# control_board-ATSAMD21.net
KiCad netlist of a schematic drawn in EAGLE
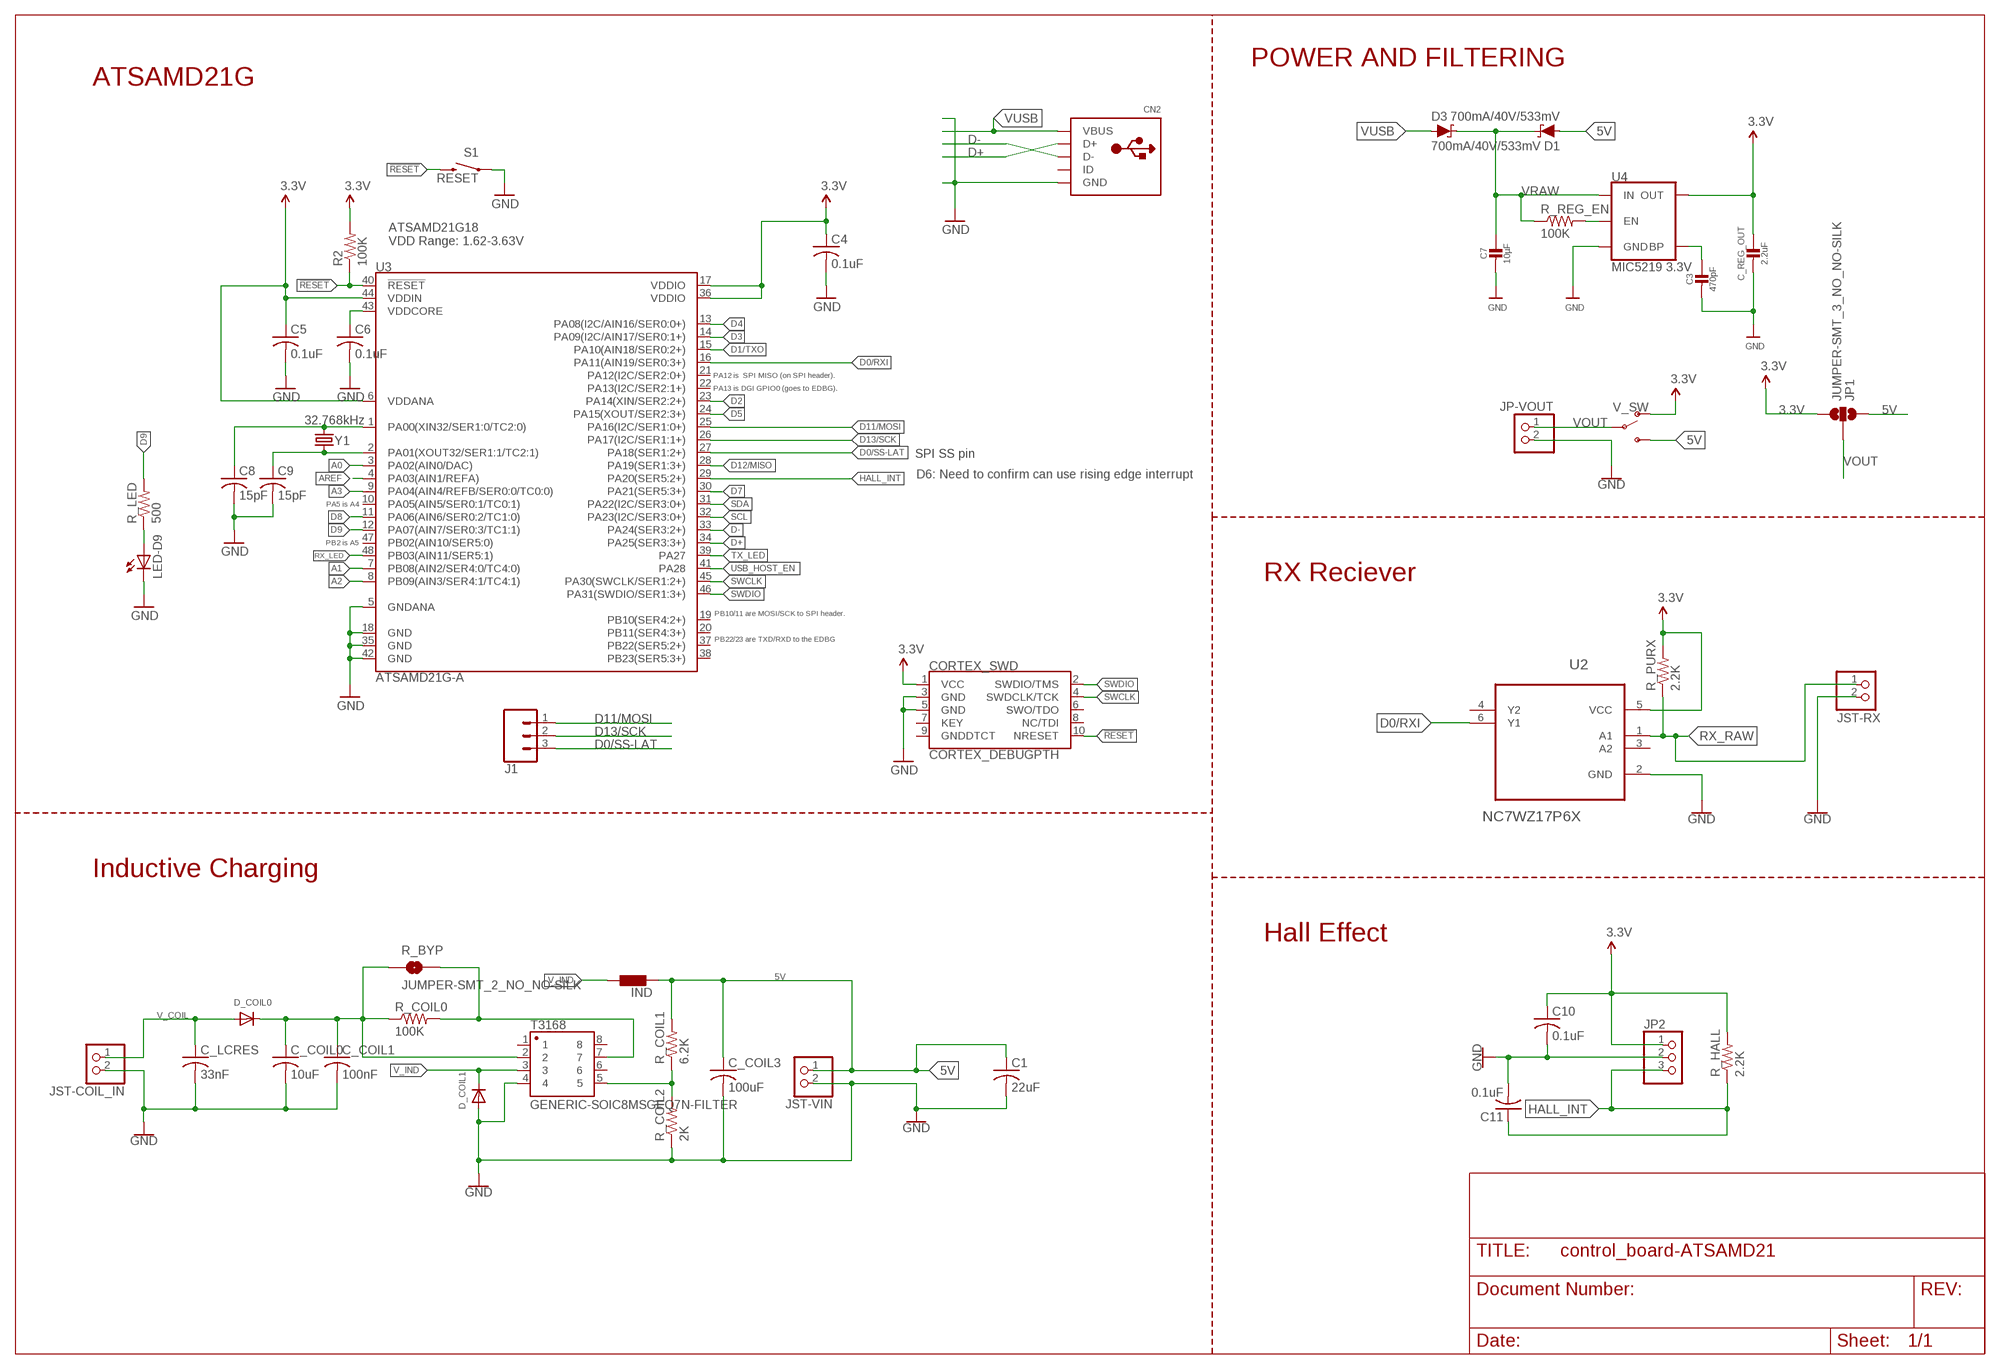
[diagram p0: schematic, sheet 1]

(export (version "E")
  (design (tool "Eeschema 10.0.6"))
  (components
    (comp (ref "C1")
      (value "22uF")
      (footprint "eagle-import:C1206")
      (libsource (lib "eagle-import") (part "C-USC1206"))
    )
    (comp (ref "C3")
      (value "470pF")
      (footprint "eagle-import:0603-NO")
      (libsource (lib "eagle-import") (part "CAP_CERAMIC0603_NO"))
    )
    (comp (ref "C4")
      (value "0.1uF")
      (footprint "eagle-import:C0603")
      (libsource (lib "eagle-import") (part "C-USC0603"))
    )
    (comp (ref "C5")
      (value "0.1uF")
      (footprint "eagle-import:C0603")
      (libsource (lib "eagle-import") (part "C-USC0603"))
    )
    (comp (ref "C6")
      (value "0.1uF")
      (footprint "eagle-import:C0603")
      (libsource (lib "eagle-import") (part "C-USC0603"))
    )
    (comp (ref "C7")
      (value "10µF")
      (footprint "eagle-import:0805-NO")
      (libsource (lib "eagle-import") (part "CAP_CERAMIC0805-NOOUTLINE"))
    )
    (comp (ref "C8")
      (value "15pF")
      (footprint "eagle-import:C0603")
      (libsource (lib "eagle-import") (part "C-USC0603"))
    )
    (comp (ref "C9")
      (value "15pF")
      (footprint "eagle-import:C0603")
      (libsource (lib "eagle-import") (part "C-USC0603"))
    )
    (comp (ref "C10")
      (value "0.1uF")
      (footprint "eagle-import:C0603")
      (libsource (lib "eagle-import") (part "C-USC0603"))
    )
    (comp (ref "C11")
      (value "0.1uF")
      (footprint "eagle-import:C0603")
      (libsource (lib "eagle-import") (part "C-USC0603"))
    )
    (comp (ref "CN2")
      (value "USBTHM")
      (footprint "eagle-import:USB-MINIB-THM")
      (libsource (lib "eagle-import") (part "USBTHM"))
    )
    (comp (ref "CORTEX_SWD")
      (value "CORTEX_DEBUGPTH")
      (footprint "eagle-import:2X5-PTH-1.27MM")
      (libsource (lib "eagle-import") (part "CORTEX_DEBUGPTH"))
    )
    (comp (ref "C_COIL0")
      (value "10uF")
      (footprint "eagle-import:C1206")
      (libsource (lib "eagle-import") (part "C-USC1206"))
    )
    (comp (ref "C_COIL1")
      (value "100nF")
      (footprint "eagle-import:C1206")
      (libsource (lib "eagle-import") (part "C-USC1206"))
    )
    (comp (ref "C_COIL3")
      (value "100uF")
      (footprint "eagle-import:C1206")
      (libsource (lib "eagle-import") (part "C-USC1206"))
    )
    (comp (ref "C_LCRES")
      (value "33nF")
      (footprint "eagle-import:C1206")
      (libsource (lib "eagle-import") (part "C-USC1206"))
    )
    (comp (ref "C_REG_OUT")
      (value "2.2uF")
      (footprint "eagle-import:0805-NO")
      (libsource (lib "eagle-import") (part "CAP_CERAMIC0805-NOOUTLINE"))
    )
    (comp (ref "D1")
      (value "700mA/40V/533mV")
      (footprint "eagle-import:SOT23-3")
      (libsource (lib "eagle-import") (part "DIODE-SCHOTTKY-ZLLS500"))
    )
    (comp (ref "D3")
      (value "700mA/40V/533mV")
      (footprint "eagle-import:SOT23-3")
      (libsource (lib "eagle-import") (part "DIODE-SCHOTTKY-ZLLS500"))
    )
    (comp (ref "D_COIL0")
      (value "DIODESMA")
      (footprint "eagle-import:SMADIODE")
      (libsource (lib "eagle-import") (part "DIODESMA"))
    )
    (comp (ref "D_COIL1")
      (value "DIODE_SOD-123FL")
      (footprint "eagle-import:SOD-123FL")
      (libsource (lib "eagle-import") (part "DIODE_SOD-123FL"))
    )
    (comp (ref "IND")
      (value "LL3230M")
      (footprint "eagle-import:L3230M")
      (libsource (lib "eagle-import") (part "LL3230M"))
    )
    (comp (ref "J1")
      (value "CONN_031X03_NO_SILK")
      (footprint "eagle-import:1X03_NO_SILK")
      (libsource (lib "eagle-import") (part "CONN_031X03_NO_SILK"))
    )
    (comp (ref "JP-VOUT")
      (value "PINHD-1X2")
      (footprint "eagle-import:1X02")
      (libsource (lib "eagle-import") (part "PINHD-1X2"))
    )
    (comp (ref "JP1")
      (value "JUMPER-SMT_3_NO_NO-SILK")
      (footprint "eagle-import:SMT-JUMPER_3_NO_NO-SILK")
      (libsource (lib "eagle-import") (part "JUMPER-SMT_3_NO_NO-SILK"))
    )
    (comp (ref "JP2")
      (value "PINHD-1X3")
      (footprint "eagle-import:1X03")
      (libsource (lib "eagle-import") (part "PINHD-1X3"))
    )
    (comp (ref "JST-COIL_IN")
      (value "JST_2PIN-THM-RA")
      (footprint "eagle-import:JST-PH-2-THM-RA")
      (libsource (lib "eagle-import") (part "JST_2PIN-THM-RA"))
    )
    (comp (ref "JST-RX")
      (value "JST_2PIN-THM-RA")
      (footprint "eagle-import:JST-PH-2-THM-RA")
      (libsource (lib "eagle-import") (part "JST_2PIN-THM-RA"))
    )
    (comp (ref "JST-VIN")
      (value "JST_2PIN-THM-RA")
      (footprint "eagle-import:JST-PH-2-THM-RA")
      (libsource (lib "eagle-import") (part "JST_2PIN-THM-RA"))
    )
    (comp (ref "LED-D9")
      (value "LEDCHIPLED_0603")
      (footprint "eagle-import:CHIPLED_0603")
      (libsource (lib "eagle-import") (part "LEDCHIPLED_0603"))
    )
    (comp (ref "R2")
      (value "100K")
      (footprint "eagle-import:0603-RES")
      (libsource (lib "eagle-import") (part "10KOHM-1/10W-1%(0603)0603"))
    )
    (comp (ref "R_BYP")
      (value "JUMPER-SMT_2_NO_NO-SILK")
      (footprint "eagle-import:SMT-JUMPER_2_NO_NO-SILK")
      (libsource (lib "eagle-import") (part "JUMPER-SMT_2_NO_NO-SILK"))
    )
    (comp (ref "R_COIL0")
      (value "100K")
      (footprint "eagle-import:R0603")
      (libsource (lib "eagle-import") (part "R-US_R0603"))
    )
    (comp (ref "R_COIL1")
      (value "6.2K")
      (footprint "eagle-import:R0603")
      (libsource (lib "eagle-import") (part "R-US_R0603"))
    )
    (comp (ref "R_COIL2")
      (value "2K")
      (footprint "eagle-import:R0603")
      (libsource (lib "eagle-import") (part "R-US_R0603"))
    )
    (comp (ref "R_HALL")
      (value "2.2K")
      (footprint "eagle-import:R0805")
      (libsource (lib "eagle-import") (part "R-US_R0805"))
    )
    (comp (ref "R_LED")
      (value "500")
      (footprint "eagle-import:R0603")
      (libsource (lib "eagle-import") (part "R-US_R0603"))
    )
    (comp (ref "R_PURX")
      (value "2.2K")
      (footprint "eagle-import:R0603")
      (libsource (lib "eagle-import") (part "R-US_R0603"))
    )
    (comp (ref "R_REG_EN")
      (value "100K")
      (footprint "eagle-import:R0603")
      (libsource (lib "eagle-import") (part "R-US_R0603"))
    )
    (comp (ref "S1")
      (value "RESET")
      (footprint "eagle-import:TACTILE_SWITCH_SMD_4.6X2.8MM")
      (libsource (lib "eagle-import") (part "SWITCH-MOMENTARY-2SMD-4.6X2.8MM"))
    )
    (comp (ref "T3168")
      (value "GENERIC-SOIC8MSGEQ7N-FILTER")
      (footprint "eagle-import:SO08")
      (libsource (lib "eagle-import") (part "GENERIC-SOIC8MSGEQ7N-FILTER"))
    )
    (comp (ref "U2")
      (value "NC7WZ17P6X")
      (footprint "eagle-import:SOT65P210X110-6N")
      (fields (field (name "MF") "Fairchild Semiconductor"))
      (libsource (lib "eagle-import") (part "NC7WZ17P6X"))
    )
    (comp (ref "U3")
      (value "ATSAMD21G-A")
      (footprint "eagle-import:TQFP-48")
      (libsource (lib "eagle-import") (part "ATSAMD21G-A"))
    )
    (comp (ref "U4")
      (value "MIC5219 3.3V")
      (footprint "eagle-import:SOT23-5")
      (libsource (lib "eagle-import") (part "V_REG_MIC52193.3V"))
    )
    (comp (ref "V_SW")
      (value "SWITCH-SPDT-SMD-RIGHT-ANGLE")
      (footprint "eagle-import:SWITCH_SPST_SMD_A")
      (libsource (lib "eagle-import") (part "SWITCH-SPDT-SMD-RIGHT-ANGLE"))
    )
    (comp (ref "Y1")
      (value "32.768kHz")
      (footprint "eagle-import:CRYSTAL-SMD-3.2X1.5MM")
      (libsource (lib "eagle-import") (part "CRYSTAL3.2X1.5MM"))
    )
  )
  (nets
    (net (code "1") (name "/VOUT") (class "Default")
      (node (ref "JP-VOUT") (pin "1") (pinfunction "1_1") (pintype "passive"))
      (node (ref "JP1") (pin "2") (pinfunction "2_2") (pintype "passive"))
      (node (ref "V_SW") (pin "2") (pinfunction "P_2") (pintype "passive"))
    )
    (net (code "2") (name "/VRAW") (class "Default")
      (node (ref "C7") (pin "1") (pinfunction "1_1") (pintype "passive"))
      (node (ref "D1") (pin "3") (pinfunction "C_3") (pintype "passive"))
      (node (ref "D3") (pin "3") (pinfunction "C_3") (pintype "passive"))
      (node (ref "R_REG_EN") (pin "1") (pinfunction "1_1") (pintype "passive"))
      (node (ref "U4") (pin "1") (pinfunction "IN_1") (pintype "input"))
    )
    (net (code "3") (name "/V_COIL") (class "Default")
      (node (ref "C_LCRES") (pin "1") (pinfunction "1_1") (pintype "passive"))
      (node (ref "D_COIL0") (pin "A") (pinfunction "A_A") (pintype "passive"))
      (node (ref "JST-COIL_IN") (pin "1") (pinfunction "2_1") (pintype "passive"))
    )
    (net (code "4") (name "/~{RESET}") (class "Default")
      (node (ref "CORTEX_SWD") (pin "10") (pinfunction "NRESET_10") (pintype "bidirectional"))
      (node (ref "R2") (pin "1") (pinfunction "1_1") (pintype "passive"))
      (node (ref "S1") (pin "3") (pinfunction "2_3") (pintype "passive"))
      (node (ref "S1") (pin "4") (pinfunction "2_4") (pintype "passive"))
      (node (ref "U3") (pin "40") (pinfunction "~{RESET}_40") (pintype "bidirectional"))
    )
    (net (code "5") (name "3.3V") (class "Default")
      (node (ref "C10") (pin "1") (pinfunction "1_1") (pintype "passive"))
      (node (ref "C4") (pin "1") (pinfunction "1_1") (pintype "passive"))
      (node (ref "C5") (pin "1") (pinfunction "1_1") (pintype "passive"))
      (node (ref "CORTEX_SWD") (pin "1") (pinfunction "VCC_1") (pintype "bidirectional"))
      (node (ref "C_REG_OUT") (pin "1") (pinfunction "1_1") (pintype "passive"))
      (node (ref "JP1") (pin "3") (pinfunction "3_3") (pintype "passive"))
      (node (ref "JP2") (pin "1") (pinfunction "1_1") (pintype "passive"))
      (node (ref "R2") (pin "2") (pinfunction "2_2") (pintype "passive"))
      (node (ref "R_HALL") (pin "2") (pinfunction "2_2") (pintype "passive"))
      (node (ref "R_PURX") (pin "2") (pinfunction "2_2") (pintype "passive"))
      (node (ref "U2") (pin "5") (pinfunction "VCC_5") (pintype "power_in"))
      (node (ref "U3") (pin "17") (pinfunction "VDDIO_17") (pintype "bidirectional"))
      (node (ref "U3") (pin "36") (pinfunction "VDDIO_36") (pintype "bidirectional"))
      (node (ref "U3") (pin "44") (pinfunction "VDDIN_44") (pintype "bidirectional"))
      (node (ref "U3") (pin "6") (pinfunction "VDDANA_6") (pintype "bidirectional"))
      (node (ref "U4") (pin "5") (pinfunction "OUT_5") (pintype "passive"))
      (node (ref "V_SW") (pin "1") (pinfunction "O_1") (pintype "passive"))
    )
    (net (code "6") (name "5V") (class "Default")
      (node (ref "C1") (pin "1") (pinfunction "1_1") (pintype "passive"))
      (node (ref "C_COIL3") (pin "1") (pinfunction "1_1") (pintype "passive"))
      (node (ref "D1") (pin "1") (pinfunction "A_1") (pintype "passive"))
      (node (ref "IND") (pin "2") (pinfunction "2_2") (pintype "passive"))
      (node (ref "JP1") (pin "1") (pinfunction "1_1") (pintype "passive"))
      (node (ref "JST-VIN") (pin "1") (pinfunction "2_1") (pintype "passive"))
      (node (ref "R_COIL1") (pin "2") (pinfunction "2_2") (pintype "passive"))
      (node (ref "V_SW") (pin "3") (pinfunction "S_3") (pintype "passive"))
    )
    (net (code "7") (name "A0") (class "Default")
      (node (ref "U3") (pin "3") (pinfunction "PA02(AIN0/DAC)_3") (pintype "bidirectional"))
    )
    (net (code "8") (name "A1") (class "Default")
      (node (ref "U3") (pin "7") (pinfunction "PB08(AIN2/SER4:0/TC4:0)_7") (pintype "bidirectional"))
    )
    (net (code "9") (name "A2") (class "Default")
      (node (ref "U3") (pin "8") (pinfunction "PB09(AIN3/SER4:1/TC4:1)_8") (pintype "bidirectional"))
    )
    (net (code "10") (name "A3") (class "Default")
      (node (ref "U3") (pin "9") (pinfunction "PA04(AIN4/REFB/SER0:0/TC0:0)_9") (pintype "bidirectional"))
    )
    (net (code "11") (name "AREF") (class "Default")
      (node (ref "U3") (pin "4") (pinfunction "PA03(AIN1/REFA)_4") (pintype "bidirectional"))
    )
    (net (code "12") (name "D+") (class "Default")
      (node (ref "CN2") (pin "D+") (pinfunction "D+_D+") (pintype "bidirectional"))
      (node (ref "U3") (pin "34") (pinfunction "PA25(SER3:3+)_34") (pintype "bidirectional"))
    )
    (net (code "13") (name "D-") (class "Default")
      (node (ref "CN2") (pin "D-") (pinfunction "D-_D-") (pintype "bidirectional"))
      (node (ref "U3") (pin "33") (pinfunction "PA24(SER3:2+)_33") (pintype "bidirectional"))
    )
    (net (code "14") (name "D0{slash}RXI") (class "Default")
      (node (ref "U2") (pin "6") (pinfunction "Y1_6") (pintype "output"))
      (node (ref "U3") (pin "16") (pinfunction "PA11(AIN19/SER0:3+)_16") (pintype "bidirectional"))
    )
    (net (code "15") (name "D0{slash}SS-LAT") (class "Default")
      (node (ref "J1") (pin "3") (pinfunction "3_3") (pintype "passive"))
      (node (ref "U3") (pin "27") (pinfunction "PA18(SER1:2+)_27") (pintype "bidirectional"))
    )
    (net (code "16") (name "D1{slash}TXO") (class "Default")
      (node (ref "U3") (pin "15") (pinfunction "PA10(AIN18/SER0:2+)_15") (pintype "bidirectional"))
    )
    (net (code "17") (name "D2") (class "Default")
      (node (ref "U3") (pin "23") (pinfunction "PA14(XIN/SER2:2+)_23") (pintype "bidirectional"))
    )
    (net (code "18") (name "D3") (class "Default")
      (node (ref "U3") (pin "14") (pinfunction "PA09(I2C/AIN17/SER0:1+)_14") (pintype "bidirectional"))
    )
    (net (code "19") (name "D4") (class "Default")
      (node (ref "U3") (pin "13") (pinfunction "PA08(I2C/AIN16/SER0:0+)_13") (pintype "bidirectional"))
    )
    (net (code "20") (name "D5") (class "Default")
      (node (ref "U3") (pin "24") (pinfunction "PA15(XOUT/SER2:3+)_24") (pintype "bidirectional"))
    )
    (net (code "21") (name "D7") (class "Default")
      (node (ref "U3") (pin "30") (pinfunction "PA21(SER5:3+)_30") (pintype "bidirectional"))
    )
    (net (code "22") (name "D8") (class "Default")
      (node (ref "U3") (pin "11") (pinfunction "PA06(AIN6/SER0:2/TC1:0)_11") (pintype "bidirectional"))
    )
    (net (code "23") (name "D9") (class "Default")
      (node (ref "R_LED") (pin "2") (pinfunction "2_2") (pintype "passive"))
      (node (ref "U3") (pin "12") (pinfunction "PA07(AIN7/SER0:3/TC1:1)_12") (pintype "bidirectional"))
    )
    (net (code "24") (name "D11{slash}MOSI") (class "Default")
      (node (ref "J1") (pin "1") (pinfunction "1_1") (pintype "passive"))
      (node (ref "U3") (pin "25") (pinfunction "PA16(I2C/SER1:0+)_25") (pintype "bidirectional"))
    )
    (net (code "25") (name "D12{slash}MISO") (class "Default")
      (node (ref "U3") (pin "28") (pinfunction "PA19(SER1:3+)_28") (pintype "bidirectional"))
    )
    (net (code "26") (name "D13{slash}SCK") (class "Default")
      (node (ref "J1") (pin "2") (pinfunction "2_2") (pintype "passive"))
      (node (ref "U3") (pin "26") (pinfunction "PA17(I2C/SER1:1+)_26") (pintype "bidirectional"))
    )
    (net (code "27") (name "GND") (class "Default")
      (node (ref "C1") (pin "2") (pinfunction "2_2") (pintype "passive"))
      (node (ref "C10") (pin "2") (pinfunction "2_2") (pintype "passive"))
      (node (ref "C11") (pin "2") (pinfunction "2_2") (pintype "passive"))
      (node (ref "C3") (pin "2") (pinfunction "2_2") (pintype "passive"))
      (node (ref "C4") (pin "2") (pinfunction "2_2") (pintype "passive"))
      (node (ref "C5") (pin "2") (pinfunction "2_2") (pintype "passive"))
      (node (ref "C6") (pin "2") (pinfunction "2_2") (pintype "passive"))
      (node (ref "C7") (pin "2") (pinfunction "2_2") (pintype "passive"))
      (node (ref "C8") (pin "2") (pinfunction "2_2") (pintype "passive"))
      (node (ref "C9") (pin "2") (pinfunction "2_2") (pintype "passive"))
      (node (ref "CN2") (pin "GND") (pinfunction "GND_GND") (pintype "power_in"))
      (node (ref "CORTEX_SWD") (pin "3") (pinfunction "GND_3") (pintype "bidirectional"))
      (node (ref "CORTEX_SWD") (pin "5") (pinfunction "GND_5") (pintype "bidirectional"))
      (node (ref "C_COIL0") (pin "2") (pinfunction "2_2") (pintype "passive"))
      (node (ref "C_COIL1") (pin "2") (pinfunction "2_2") (pintype "passive"))
      (node (ref "C_COIL3") (pin "2") (pinfunction "2_2") (pintype "passive"))
      (node (ref "C_LCRES") (pin "2") (pinfunction "2_2") (pintype "passive"))
      (node (ref "C_REG_OUT") (pin "2") (pinfunction "2_2") (pintype "passive"))
      (node (ref "D_COIL1") (pin "A") (pinfunction "A_A") (pintype "passive"))
      (node (ref "JP-VOUT") (pin "2") (pinfunction "2_2") (pintype "passive"))
      (node (ref "JP2") (pin "2") (pinfunction "2_2") (pintype "passive"))
      (node (ref "JST-COIL_IN") (pin "2") (pinfunction "1_2") (pintype "passive"))
      (node (ref "JST-RX") (pin "2") (pinfunction "1_2") (pintype "passive"))
      (node (ref "JST-VIN") (pin "2") (pinfunction "1_2") (pintype "passive"))
      (node (ref "LED-D9") (pin "C") (pinfunction "C_C") (pintype "passive"))
      (node (ref "R_COIL2") (pin "1") (pinfunction "1_1") (pintype "passive"))
      (node (ref "S1") (pin "1") (pinfunction "1_1") (pintype "passive"))
      (node (ref "S1") (pin "2") (pinfunction "1_2") (pintype "passive"))
      (node (ref "T3168") (pin "4") (pinfunction "4_4") (pintype "bidirectional"))
      (node (ref "U2") (pin "2") (pinfunction "GND_2") (pintype "passive"))
      (node (ref "U3") (pin "18") (pinfunction "GND_18") (pintype "bidirectional"))
      (node (ref "U3") (pin "35") (pinfunction "GND_35") (pintype "bidirectional"))
      (node (ref "U3") (pin "42") (pinfunction "GND_42") (pintype "bidirectional"))
      (node (ref "U3") (pin "5") (pinfunction "GNDANA_5") (pintype "bidirectional"))
      (node (ref "U4") (pin "2") (pinfunction "GND_2") (pintype "input"))
    )
    (net (code "28") (name "HALL_INT") (class "Default")
      (node (ref "C11") (pin "1") (pinfunction "1_1") (pintype "passive"))
      (node (ref "JP2") (pin "3") (pinfunction "3_3") (pintype "passive"))
      (node (ref "R_HALL") (pin "1") (pinfunction "1_1") (pintype "passive"))
      (node (ref "U3") (pin "29") (pinfunction "PA20(SER5:2+)_29") (pintype "bidirectional"))
    )
    (net (code "29") (name "Net-(C_COIL0-Pad1)") (class "Default")
      (node (ref "C_COIL0") (pin "1") (pinfunction "1_1") (pintype "passive"))
      (node (ref "C_COIL1") (pin "1") (pinfunction "1_1") (pintype "passive"))
      (node (ref "D_COIL0") (pin "C") (pinfunction "C_C") (pintype "passive"))
      (node (ref "R_BYP") (pin "1") (pinfunction "1_1") (pintype "passive"))
      (node (ref "R_COIL0") (pin "1") (pinfunction "1_1") (pintype "passive"))
      (node (ref "T3168") (pin "2") (pinfunction "2_2") (pintype "bidirectional"))
    )
    (net (code "30") (name "Net-(LED-D9-PadA)") (class "Default")
      (node (ref "LED-D9") (pin "A") (pinfunction "A_A") (pintype "passive"))
      (node (ref "R_LED") (pin "1") (pinfunction "1_1") (pintype "passive"))
    )
    (net (code "31") (name "Net-(R_BYP-Pad2)") (class "Default")
      (node (ref "R_BYP") (pin "2") (pinfunction "2_2") (pintype "passive"))
      (node (ref "R_COIL0") (pin "2") (pinfunction "2_2") (pintype "passive"))
      (node (ref "T3168") (pin "7") (pinfunction "7_7") (pintype "bidirectional"))
    )
    (net (code "32") (name "Net-(R_COIL1-Pad1)") (class "Default")
      (node (ref "R_COIL1") (pin "1") (pinfunction "1_1") (pintype "passive"))
      (node (ref "R_COIL2") (pin "2") (pinfunction "2_2") (pintype "passive"))
      (node (ref "T3168") (pin "5") (pinfunction "5_5") (pintype "bidirectional"))
    )
    (net (code "33") (name "Net-(U3-PA00(XIN32{slash}SER1:0{slash}TC2:0))") (class "Default")
      (node (ref "C8") (pin "1") (pinfunction "1_1") (pintype "passive"))
      (node (ref "U3") (pin "1") (pinfunction "PA00(XIN32/SER1:0/TC2:0)_1") (pintype "bidirectional"))
      (node (ref "Y1") (pin "P$2") (pinfunction "2_P$2") (pintype "passive"))
    )
    (net (code "34") (name "Net-(U3-PA01(XOUT32{slash}SER1:1{slash}TC2:1))") (class "Default")
      (node (ref "C9") (pin "1") (pinfunction "1_1") (pintype "passive"))
      (node (ref "U3") (pin "2") (pinfunction "PA01(XOUT32/SER1:1/TC2:1)_2") (pintype "bidirectional"))
      (node (ref "Y1") (pin "P$1") (pinfunction "1_P$1") (pintype "passive"))
    )
    (net (code "35") (name "Net-(U3-VDDCORE)") (class "Default")
      (node (ref "C6") (pin "1") (pinfunction "1_1") (pintype "passive"))
      (node (ref "U3") (pin "43") (pinfunction "VDDCORE_43") (pintype "bidirectional"))
    )
    (net (code "36") (name "Net-(U4-BP)") (class "Default")
      (node (ref "C3") (pin "1") (pinfunction "1_1") (pintype "passive"))
      (node (ref "U4") (pin "4") (pinfunction "BP_4") (pintype "input"))
    )
    (net (code "37") (name "Net-(U4-EN)") (class "Default")
      (node (ref "R_REG_EN") (pin "2") (pinfunction "2_2") (pintype "passive"))
      (node (ref "U4") (pin "3") (pinfunction "EN_3") (pintype "input"))
    )
    (net (code "38") (name "RX_LED") (class "Default")
      (node (ref "U3") (pin "48") (pinfunction "PB03(AIN11/SER5:1)_48") (pintype "bidirectional"))
    )
    (net (code "39") (name "RX_RAW") (class "Default")
      (node (ref "JST-RX") (pin "1") (pinfunction "2_1") (pintype "passive"))
      (node (ref "R_PURX") (pin "1") (pinfunction "1_1") (pintype "passive"))
      (node (ref "U2") (pin "1") (pinfunction "A1_1") (pintype "input"))
    )
    (net (code "40") (name "SCL") (class "Default")
      (node (ref "U3") (pin "32") (pinfunction "PA23(I2C/SER3:0+)_32") (pintype "bidirectional"))
    )
    (net (code "41") (name "SDA") (class "Default")
      (node (ref "U3") (pin "31") (pinfunction "PA22(I2C/SER3:0+)_31") (pintype "bidirectional"))
    )
    (net (code "42") (name "SWCLK") (class "Default")
      (node (ref "CORTEX_SWD") (pin "4") (pinfunction "SWDCLK/TCK_4") (pintype "bidirectional"))
      (node (ref "U3") (pin "45") (pinfunction "PA30(SWCLK/SER1:2+)_45") (pintype "bidirectional"))
    )
    (net (code "43") (name "SWDIO") (class "Default")
      (node (ref "CORTEX_SWD") (pin "2") (pinfunction "SWDIO/TMS_2") (pintype "bidirectional"))
      (node (ref "U3") (pin "46") (pinfunction "PA31(SWDIO/SER1:3+)_46") (pintype "bidirectional"))
    )
    (net (code "44") (name "TX_LED") (class "Default")
      (node (ref "U3") (pin "39") (pinfunction "PA27_39") (pintype "bidirectional"))
    )
    (net (code "45") (name "USB_HOST_EN") (class "Default")
      (node (ref "U3") (pin "41") (pinfunction "PA28_41") (pintype "bidirectional"))
    )
    (net (code "46") (name "VUSB") (class "Default")
      (node (ref "CN2") (pin "VBUS") (pinfunction "VBUS_VBUS") (pintype "power_in"))
      (node (ref "D3") (pin "1") (pinfunction "A_1") (pintype "passive"))
    )
    (net (code "47") (name "V_IND") (class "Default")
      (node (ref "D_COIL1") (pin "C") (pinfunction "C_C") (pintype "passive"))
      (node (ref "IND") (pin "1") (pinfunction "1_1") (pintype "passive"))
      (node (ref "T3168") (pin "3") (pinfunction "3_3") (pintype "bidirectional"))
    )
    (net (code "48") (name "unconnected-(CN2-PadID)") (class "Default")
      (node (ref "CN2") (pin "ID") (pinfunction "ID_ID") (pintype "bidirectional"))
    )
    (net (code "49") (name "unconnected-(CORTEX_SWD-GNDDTCT-Pad9)") (class "Default")
      (node (ref "CORTEX_SWD") (pin "9") (pinfunction "GNDDTCT_9") (pintype "bidirectional"))
    )
    (net (code "50") (name "unconnected-(CORTEX_SWD-KEY-Pad7)") (class "Default")
      (node (ref "CORTEX_SWD") (pin "7") (pinfunction "KEY_7") (pintype "bidirectional"))
    )
    (net (code "51") (name "unconnected-(CORTEX_SWD-NC{slash}TDI-Pad8)") (class "Default")
      (node (ref "CORTEX_SWD") (pin "8") (pinfunction "NC/TDI_8") (pintype "bidirectional"))
    )
    (net (code "52") (name "unconnected-(CORTEX_SWD-SWO{slash}TDO-Pad6)") (class "Default")
      (node (ref "CORTEX_SWD") (pin "6") (pinfunction "SWO/TDO_6") (pintype "bidirectional"))
    )
    (net (code "53") (name "unconnected-(T3168-Pad1)") (class "Default")
      (node (ref "T3168") (pin "1") (pinfunction "1_1") (pintype "bidirectional"))
    )
    (net (code "54") (name "unconnected-(T3168-Pad6)") (class "Default")
      (node (ref "T3168") (pin "6") (pinfunction "6_6") (pintype "bidirectional"))
    )
    (net (code "55") (name "unconnected-(T3168-Pad8)") (class "Default")
      (node (ref "T3168") (pin "8") (pinfunction "8_8") (pintype "bidirectional"))
    )
    (net (code "56") (name "unconnected-(U2-A2-Pad3)") (class "Default")
      (node (ref "U2") (pin "3") (pinfunction "A2_3") (pintype "input"))
    )
    (net (code "57") (name "unconnected-(U2-Y2-Pad4)") (class "Default")
      (node (ref "U2") (pin "4") (pinfunction "Y2_4") (pintype "output"))
    )
    (net (code "58") (name "unconnected-(U3-PA05(AIN5{slash}SER0:1{slash}TC0:1)-Pad10)") (class "Default")
      (node (ref "U3") (pin "10") (pinfunction "PA05(AIN5/SER0:1/TC0:1)_10") (pintype "bidirectional"))
    )
    (net (code "59") (name "unconnected-(U3-PA12(I2C{slash}SER2:0+)-Pad21)") (class "Default")
      (node (ref "U3") (pin "21") (pinfunction "PA12(I2C/SER2:0+)_21") (pintype "bidirectional"))
    )
    (net (code "60") (name "unconnected-(U3-PA13(I2C{slash}SER2:1+)-Pad22)") (class "Default")
      (node (ref "U3") (pin "22") (pinfunction "PA13(I2C/SER2:1+)_22") (pintype "bidirectional"))
    )
    (net (code "61") (name "unconnected-(U3-PB02(AIN10{slash}SER5:0)-Pad47)") (class "Default")
      (node (ref "U3") (pin "47") (pinfunction "PB02(AIN10/SER5:0)_47") (pintype "bidirectional"))
    )
    (net (code "62") (name "unconnected-(U3-PB10(SER4:2+)-Pad19)") (class "Default")
      (node (ref "U3") (pin "19") (pinfunction "PB10(SER4:2+)_19") (pintype "bidirectional"))
    )
    (net (code "63") (name "unconnected-(U3-PB11(SER4:3+)-Pad20)") (class "Default")
      (node (ref "U3") (pin "20") (pinfunction "PB11(SER4:3+)_20") (pintype "bidirectional"))
    )
    (net (code "64") (name "unconnected-(U3-PB22(SER5:2+)-Pad37)") (class "Default")
      (node (ref "U3") (pin "37") (pinfunction "PB22(SER5:2+)_37") (pintype "bidirectional"))
    )
    (net (code "65") (name "unconnected-(U3-PB23(SER5:3+)-Pad38)") (class "Default")
      (node (ref "U3") (pin "38") (pinfunction "PB23(SER5:3+)_38") (pintype "bidirectional"))
    )
  )
)
